# BEP3_Test_Interface.net
KiCad netlist of a schematic drawn in EAGLE
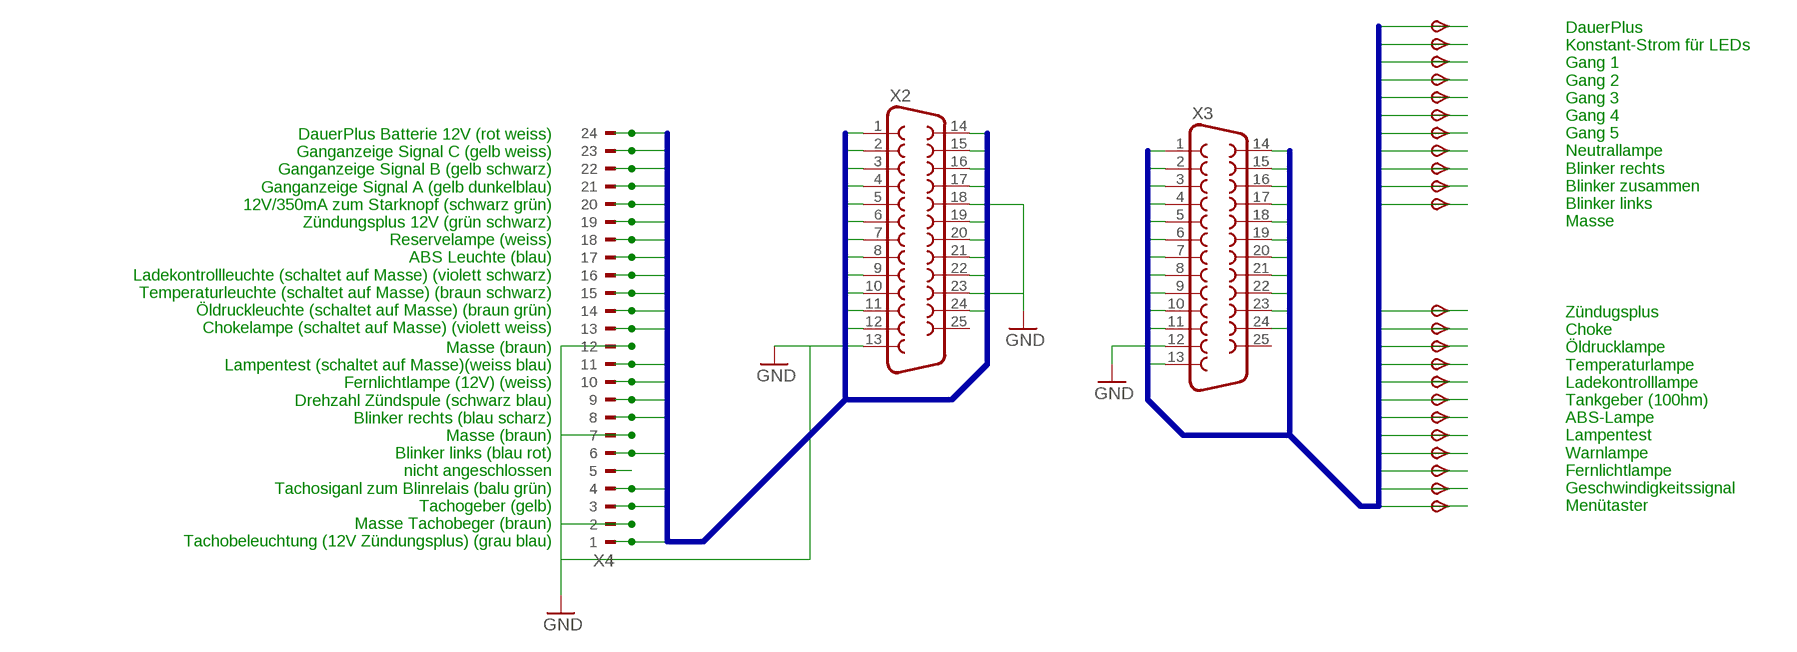
[diagram p0: schematic, sheet 1]

(export (version "E")
  (design (tool "Eeschema 10.0.6"))
  (components
    (comp (ref "TP1")
      (value "TPSFEDERPIN")
      (footprint "eagle-import:1,36ID")
      (libsource (lib "eagle-import") (part "TPSFEDERPIN"))
    )
    (comp (ref "TP2")
      (value "TPSFEDERPIN")
      (footprint "eagle-import:1,36ID")
      (libsource (lib "eagle-import") (part "TPSFEDERPIN"))
    )
    (comp (ref "TP3")
      (value "TPSFEDERPIN")
      (footprint "eagle-import:1,36ID")
      (libsource (lib "eagle-import") (part "TPSFEDERPIN"))
    )
    (comp (ref "TP4")
      (value "TPSFEDERPIN")
      (footprint "eagle-import:1,36ID")
      (libsource (lib "eagle-import") (part "TPSFEDERPIN"))
    )
    (comp (ref "TP5")
      (value "TPSFEDERPIN")
      (footprint "eagle-import:1,36ID")
      (libsource (lib "eagle-import") (part "TPSFEDERPIN"))
    )
    (comp (ref "TP6")
      (value "TPSFEDERPIN")
      (footprint "eagle-import:1,36ID")
      (libsource (lib "eagle-import") (part "TPSFEDERPIN"))
    )
    (comp (ref "TP7")
      (value "TPSFEDERPIN")
      (footprint "eagle-import:1,36ID")
      (libsource (lib "eagle-import") (part "TPSFEDERPIN"))
    )
    (comp (ref "TP8")
      (value "TPSFEDERPIN")
      (footprint "eagle-import:1,36ID")
      (libsource (lib "eagle-import") (part "TPSFEDERPIN"))
    )
    (comp (ref "TP9")
      (value "TPSFEDERPIN")
      (footprint "eagle-import:1,36ID")
      (libsource (lib "eagle-import") (part "TPSFEDERPIN"))
    )
    (comp (ref "TP10")
      (value "TPSFEDERPIN")
      (footprint "eagle-import:1,36ID")
      (libsource (lib "eagle-import") (part "TPSFEDERPIN"))
    )
    (comp (ref "TP11")
      (value "TPSFEDERPIN")
      (footprint "eagle-import:1,36ID")
      (libsource (lib "eagle-import") (part "TPSFEDERPIN"))
    )
    (comp (ref "TP12")
      (value "TPSFEDERPIN")
      (footprint "eagle-import:1,36ID")
      (libsource (lib "eagle-import") (part "TPSFEDERPIN"))
    )
    (comp (ref "TP13")
      (value "TPSFEDERPIN")
      (footprint "eagle-import:1,36ID")
      (libsource (lib "eagle-import") (part "TPSFEDERPIN"))
    )
    (comp (ref "TP16")
      (value "TPSFEDERPIN")
      (footprint "eagle-import:1,36ID")
      (libsource (lib "eagle-import") (part "TPSFEDERPIN"))
    )
    (comp (ref "TP17")
      (value "TPSFEDERPIN")
      (footprint "eagle-import:1,36ID")
      (libsource (lib "eagle-import") (part "TPSFEDERPIN"))
    )
    (comp (ref "TP18")
      (value "TPSFEDERPIN")
      (footprint "eagle-import:1,36ID")
      (libsource (lib "eagle-import") (part "TPSFEDERPIN"))
    )
    (comp (ref "TP19")
      (value "TPSFEDERPIN")
      (footprint "eagle-import:1,36ID")
      (libsource (lib "eagle-import") (part "TPSFEDERPIN"))
    )
    (comp (ref "TP21")
      (value "TPSFEDERPIN")
      (footprint "eagle-import:1,36ID")
      (libsource (lib "eagle-import") (part "TPSFEDERPIN"))
    )
    (comp (ref "TP22")
      (value "TPSFEDERPIN")
      (footprint "eagle-import:1,36ID")
      (libsource (lib "eagle-import") (part "TPSFEDERPIN"))
    )
    (comp (ref "TP23")
      (value "TPSFEDERPIN")
      (footprint "eagle-import:1,36ID")
      (libsource (lib "eagle-import") (part "TPSFEDERPIN"))
    )
    (comp (ref "TP24")
      (value "TPSFEDERPIN")
      (footprint "eagle-import:1,36ID")
      (libsource (lib "eagle-import") (part "TPSFEDERPIN"))
    )
    (comp (ref "TP25")
      (value "TPSFEDERPIN")
      (footprint "eagle-import:1,36ID")
      (libsource (lib "eagle-import") (part "TPSFEDERPIN"))
    )
    (comp (ref "TP26")
      (value "TPSFEDERPIN")
      (footprint "eagle-import:1,36ID")
      (libsource (lib "eagle-import") (part "TPSFEDERPIN"))
    )
    (comp (ref "X2")
      (value "F25H")
      (footprint "eagle-import:F25H")
      (libsource (lib "eagle-import") (part "F25H"))
    )
    (comp (ref "X3")
      (value "F25H")
      (footprint "eagle-import:F25H")
      (libsource (lib "eagle-import") (part "F25H"))
    )
    (comp (ref "X4")
      (value "CON_BMWTESTPINS")
      (footprint "eagle-import:24-TESTPIN_1,36ID")
      (libsource (lib "eagle-import") (part "CON_BMWTESTPINS"))
    )
  )
  (nets
    (net (code "1") (name "/BMW1") (class "Default")
      (node (ref "X2") (pin "1") (pinfunction "1_1") (pintype "passive"))
      (node (ref "X4") (pin "P24") (pinfunction "24_P24") (pintype "passive"))
    )
    (net (code "2") (name "/BMW2") (class "Default")
      (node (ref "X2") (pin "2") (pinfunction "2_2") (pintype "passive"))
      (node (ref "X4") (pin "P23") (pinfunction "23_P23") (pintype "passive"))
    )
    (net (code "3") (name "/BMW3") (class "Default")
      (node (ref "X2") (pin "3") (pinfunction "3_3") (pintype "passive"))
      (node (ref "X4") (pin "P22") (pinfunction "22_P22") (pintype "passive"))
    )
    (net (code "4") (name "/BMW4") (class "Default")
      (node (ref "X2") (pin "4") (pinfunction "4_4") (pintype "passive"))
      (node (ref "X4") (pin "P21") (pinfunction "21_P21") (pintype "passive"))
    )
    (net (code "5") (name "/BMW5") (class "Default")
      (node (ref "X2") (pin "5") (pinfunction "5_5") (pintype "passive"))
      (node (ref "X4") (pin "P20") (pinfunction "20_P20") (pintype "passive"))
    )
    (net (code "6") (name "/BMW6") (class "Default")
      (node (ref "X2") (pin "6") (pinfunction "6_6") (pintype "passive"))
      (node (ref "X4") (pin "P19") (pinfunction "19_P19") (pintype "passive"))
    )
    (net (code "7") (name "/BMW7") (class "Default")
      (node (ref "X2") (pin "7") (pinfunction "7_7") (pintype "passive"))
      (node (ref "X4") (pin "P18") (pinfunction "18_P18") (pintype "passive"))
    )
    (net (code "8") (name "/BMW8") (class "Default")
      (node (ref "X2") (pin "8") (pinfunction "8_8") (pintype "passive"))
      (node (ref "X4") (pin "P17") (pinfunction "17_P17") (pintype "passive"))
    )
    (net (code "9") (name "/BMW9") (class "Default")
      (node (ref "X2") (pin "9") (pinfunction "9_9") (pintype "passive"))
      (node (ref "X4") (pin "P16") (pinfunction "16_P16") (pintype "passive"))
    )
    (net (code "10") (name "/BMW10") (class "Default")
      (node (ref "X2") (pin "10") (pinfunction "10_10") (pintype "passive"))
      (node (ref "X4") (pin "P15") (pinfunction "15_P15") (pintype "passive"))
    )
    (net (code "11") (name "/BMW11") (class "Default")
      (node (ref "X2") (pin "11") (pinfunction "11_11") (pintype "passive"))
      (node (ref "X4") (pin "P14") (pinfunction "14_P14") (pintype "passive"))
    )
    (net (code "12") (name "/BMW12") (class "Default")
      (node (ref "X2") (pin "12") (pinfunction "12_12") (pintype "passive"))
      (node (ref "X4") (pin "P13") (pinfunction "13_P13") (pintype "passive"))
    )
    (net (code "13") (name "/BMW14") (class "Default")
      (node (ref "X2") (pin "14") (pinfunction "14_14") (pintype "passive"))
      (node (ref "X4") (pin "P11") (pinfunction "11_P11") (pintype "passive"))
    )
    (net (code "14") (name "/BMW15") (class "Default")
      (node (ref "X2") (pin "15") (pinfunction "15_15") (pintype "passive"))
      (node (ref "X4") (pin "P10") (pinfunction "10_P10") (pintype "passive"))
    )
    (net (code "15") (name "/BMW16") (class "Default")
      (node (ref "X2") (pin "16") (pinfunction "16_16") (pintype "passive"))
      (node (ref "X4") (pin "P9") (pinfunction "9_P9") (pintype "passive"))
    )
    (net (code "16") (name "/BMW17") (class "Default")
      (node (ref "X2") (pin "17") (pinfunction "17_17") (pintype "passive"))
      (node (ref "X4") (pin "P8") (pinfunction "8_P8") (pintype "passive"))
    )
    (net (code "17") (name "/BMW19") (class "Default")
      (node (ref "X2") (pin "19") (pinfunction "19_19") (pintype "passive"))
      (node (ref "X4") (pin "P6") (pinfunction "6_P6") (pintype "passive"))
    )
    (net (code "18") (name "/BMW21") (class "Default")
      (node (ref "X2") (pin "21") (pinfunction "21_21") (pintype "passive"))
      (node (ref "X4") (pin "P4") (pinfunction "4_P4") (pintype "passive"))
    )
    (net (code "19") (name "/BMW22") (class "Default")
      (node (ref "X2") (pin "22") (pinfunction "22_22") (pintype "passive"))
      (node (ref "X4") (pin "P3") (pinfunction "3_P3") (pintype "passive"))
    )
    (net (code "20") (name "/BMW24") (class "Default")
      (node (ref "X2") (pin "24") (pinfunction "24_24") (pintype "passive"))
      (node (ref "X4") (pin "P1") (pinfunction "1_P1") (pintype "passive"))
    )
    (net (code "21") (name "/WAGO1") (class "Default")
      (node (ref "TP1") (pin "P$1") (pinfunction "PP_P$1") (pintype "input"))
      (node (ref "X3") (pin "1") (pinfunction "1_1") (pintype "passive"))
    )
    (net (code "22") (name "/WAGO2") (class "Default")
      (node (ref "TP2") (pin "P$1") (pinfunction "PP_P$1") (pintype "input"))
      (node (ref "X3") (pin "2") (pinfunction "2_2") (pintype "passive"))
    )
    (net (code "23") (name "/WAGO3") (class "Default")
      (node (ref "TP3") (pin "P$1") (pinfunction "PP_P$1") (pintype "input"))
      (node (ref "X3") (pin "3") (pinfunction "3_3") (pintype "passive"))
    )
    (net (code "24") (name "/WAGO4") (class "Default")
      (node (ref "TP4") (pin "P$1") (pinfunction "PP_P$1") (pintype "input"))
      (node (ref "X3") (pin "4") (pinfunction "4_4") (pintype "passive"))
    )
    (net (code "25") (name "/WAGO5") (class "Default")
      (node (ref "TP5") (pin "P$1") (pinfunction "PP_P$1") (pintype "input"))
      (node (ref "X3") (pin "5") (pinfunction "5_5") (pintype "passive"))
    )
    (net (code "26") (name "/WAGO6") (class "Default")
      (node (ref "TP6") (pin "P$1") (pinfunction "PP_P$1") (pintype "input"))
      (node (ref "X3") (pin "6") (pinfunction "6_6") (pintype "passive"))
    )
    (net (code "27") (name "/WAGO7") (class "Default")
      (node (ref "TP7") (pin "P$1") (pinfunction "PP_P$1") (pintype "input"))
      (node (ref "X3") (pin "7") (pinfunction "7_7") (pintype "passive"))
    )
    (net (code "28") (name "/WAGO8") (class "Default")
      (node (ref "TP8") (pin "P$1") (pinfunction "PP_P$1") (pintype "input"))
      (node (ref "X3") (pin "8") (pinfunction "8_8") (pintype "passive"))
    )
    (net (code "29") (name "/WAGO9") (class "Default")
      (node (ref "TP9") (pin "P$1") (pinfunction "PP_P$1") (pintype "input"))
      (node (ref "X3") (pin "9") (pinfunction "9_9") (pintype "passive"))
    )
    (net (code "30") (name "/WAGO10") (class "Default")
      (node (ref "TP10") (pin "P$1") (pinfunction "PP_P$1") (pintype "input"))
      (node (ref "X3") (pin "10") (pinfunction "10_10") (pintype "passive"))
    )
    (net (code "31") (name "/WAGO11") (class "Default")
      (node (ref "TP11") (pin "P$1") (pinfunction "PP_P$1") (pintype "input"))
      (node (ref "X3") (pin "11") (pinfunction "11_11") (pintype "passive"))
    )
    (net (code "32") (name "/WAGO13") (class "Default")
      (node (ref "TP12") (pin "P$1") (pinfunction "PP_P$1") (pintype "input"))
      (node (ref "X3") (pin "13") (pinfunction "13_13") (pintype "passive"))
    )
    (net (code "33") (name "/WAGO14") (class "Default")
      (node (ref "TP16") (pin "P$1") (pinfunction "PP_P$1") (pintype "input"))
      (node (ref "X3") (pin "14") (pinfunction "14_14") (pintype "passive"))
    )
    (net (code "34") (name "/WAGO15") (class "Default")
      (node (ref "TP17") (pin "P$1") (pinfunction "PP_P$1") (pintype "input"))
      (node (ref "X3") (pin "15") (pinfunction "15_15") (pintype "passive"))
    )
    (net (code "35") (name "/WAGO16") (class "Default")
      (node (ref "TP18") (pin "P$1") (pinfunction "PP_P$1") (pintype "input"))
      (node (ref "X3") (pin "16") (pinfunction "16_16") (pintype "passive"))
    )
    (net (code "36") (name "/WAGO17") (class "Default")
      (node (ref "TP19") (pin "P$1") (pinfunction "PP_P$1") (pintype "input"))
      (node (ref "X3") (pin "17") (pinfunction "17_17") (pintype "passive"))
    )
    (net (code "37") (name "/WAGO18") (class "Default")
      (node (ref "TP21") (pin "P$1") (pinfunction "PP_P$1") (pintype "input"))
      (node (ref "X3") (pin "18") (pinfunction "18_18") (pintype "passive"))
    )
    (net (code "38") (name "/WAGO19") (class "Default")
      (node (ref "TP22") (pin "P$1") (pinfunction "PP_P$1") (pintype "input"))
      (node (ref "X3") (pin "19") (pinfunction "19_19") (pintype "passive"))
    )
    (net (code "39") (name "/WAGO20") (class "Default")
      (node (ref "TP23") (pin "P$1") (pinfunction "PP_P$1") (pintype "input"))
      (node (ref "X3") (pin "20") (pinfunction "20_20") (pintype "passive"))
    )
    (net (code "40") (name "/WAGO21") (class "Default")
      (node (ref "TP24") (pin "P$1") (pinfunction "PP_P$1") (pintype "input"))
      (node (ref "X3") (pin "21") (pinfunction "21_21") (pintype "passive"))
    )
    (net (code "41") (name "/WAGO22") (class "Default")
      (node (ref "TP25") (pin "P$1") (pinfunction "PP_P$1") (pintype "input"))
      (node (ref "X3") (pin "22") (pinfunction "22_22") (pintype "passive"))
    )
    (net (code "42") (name "/WAGO23") (class "Default")
      (node (ref "TP26") (pin "P$1") (pinfunction "PP_P$1") (pintype "input"))
      (node (ref "X3") (pin "23") (pinfunction "23_23") (pintype "passive"))
    )
    (net (code "43") (name "/WAGO24") (class "Default")
      (node (ref "TP13") (pin "P$1") (pinfunction "PP_P$1") (pintype "input"))
      (node (ref "X3") (pin "24") (pinfunction "24_24") (pintype "passive"))
    )
    (net (code "44") (name "GND") (class "Default")
      (node (ref "X2") (pin "13") (pinfunction "13_13") (pintype "passive"))
      (node (ref "X2") (pin "18") (pinfunction "18_18") (pintype "passive"))
      (node (ref "X2") (pin "23") (pinfunction "23_23") (pintype "passive"))
      (node (ref "X3") (pin "12") (pinfunction "12_12") (pintype "passive"))
      (node (ref "X4") (pin "P12") (pinfunction "12_P12") (pintype "passive"))
      (node (ref "X4") (pin "P2") (pinfunction "2_P2") (pintype "passive"))
      (node (ref "X4") (pin "P7") (pinfunction "7_P7") (pintype "passive"))
    )
    (net (code "45") (name "unconnected-(X2-Pad20)") (class "Default")
      (node (ref "X2") (pin "20") (pinfunction "20_20") (pintype "passive"))
    )
    (net (code "46") (name "unconnected-(X2-Pad25)") (class "Default")
      (node (ref "X2") (pin "25") (pinfunction "25_25") (pintype "passive"))
    )
    (net (code "47") (name "unconnected-(X3-Pad25)") (class "Default")
      (node (ref "X3") (pin "25") (pinfunction "25_25") (pintype "passive"))
    )
    (net (code "48") (name "unconnected-(X4-5-PadP5)") (class "Default")
      (node (ref "X4") (pin "P5") (pinfunction "5_P5") (pintype "passive"))
    )
  )
)
